# Power.net
KiCad netlist of a schematic drawn in Altium Designer
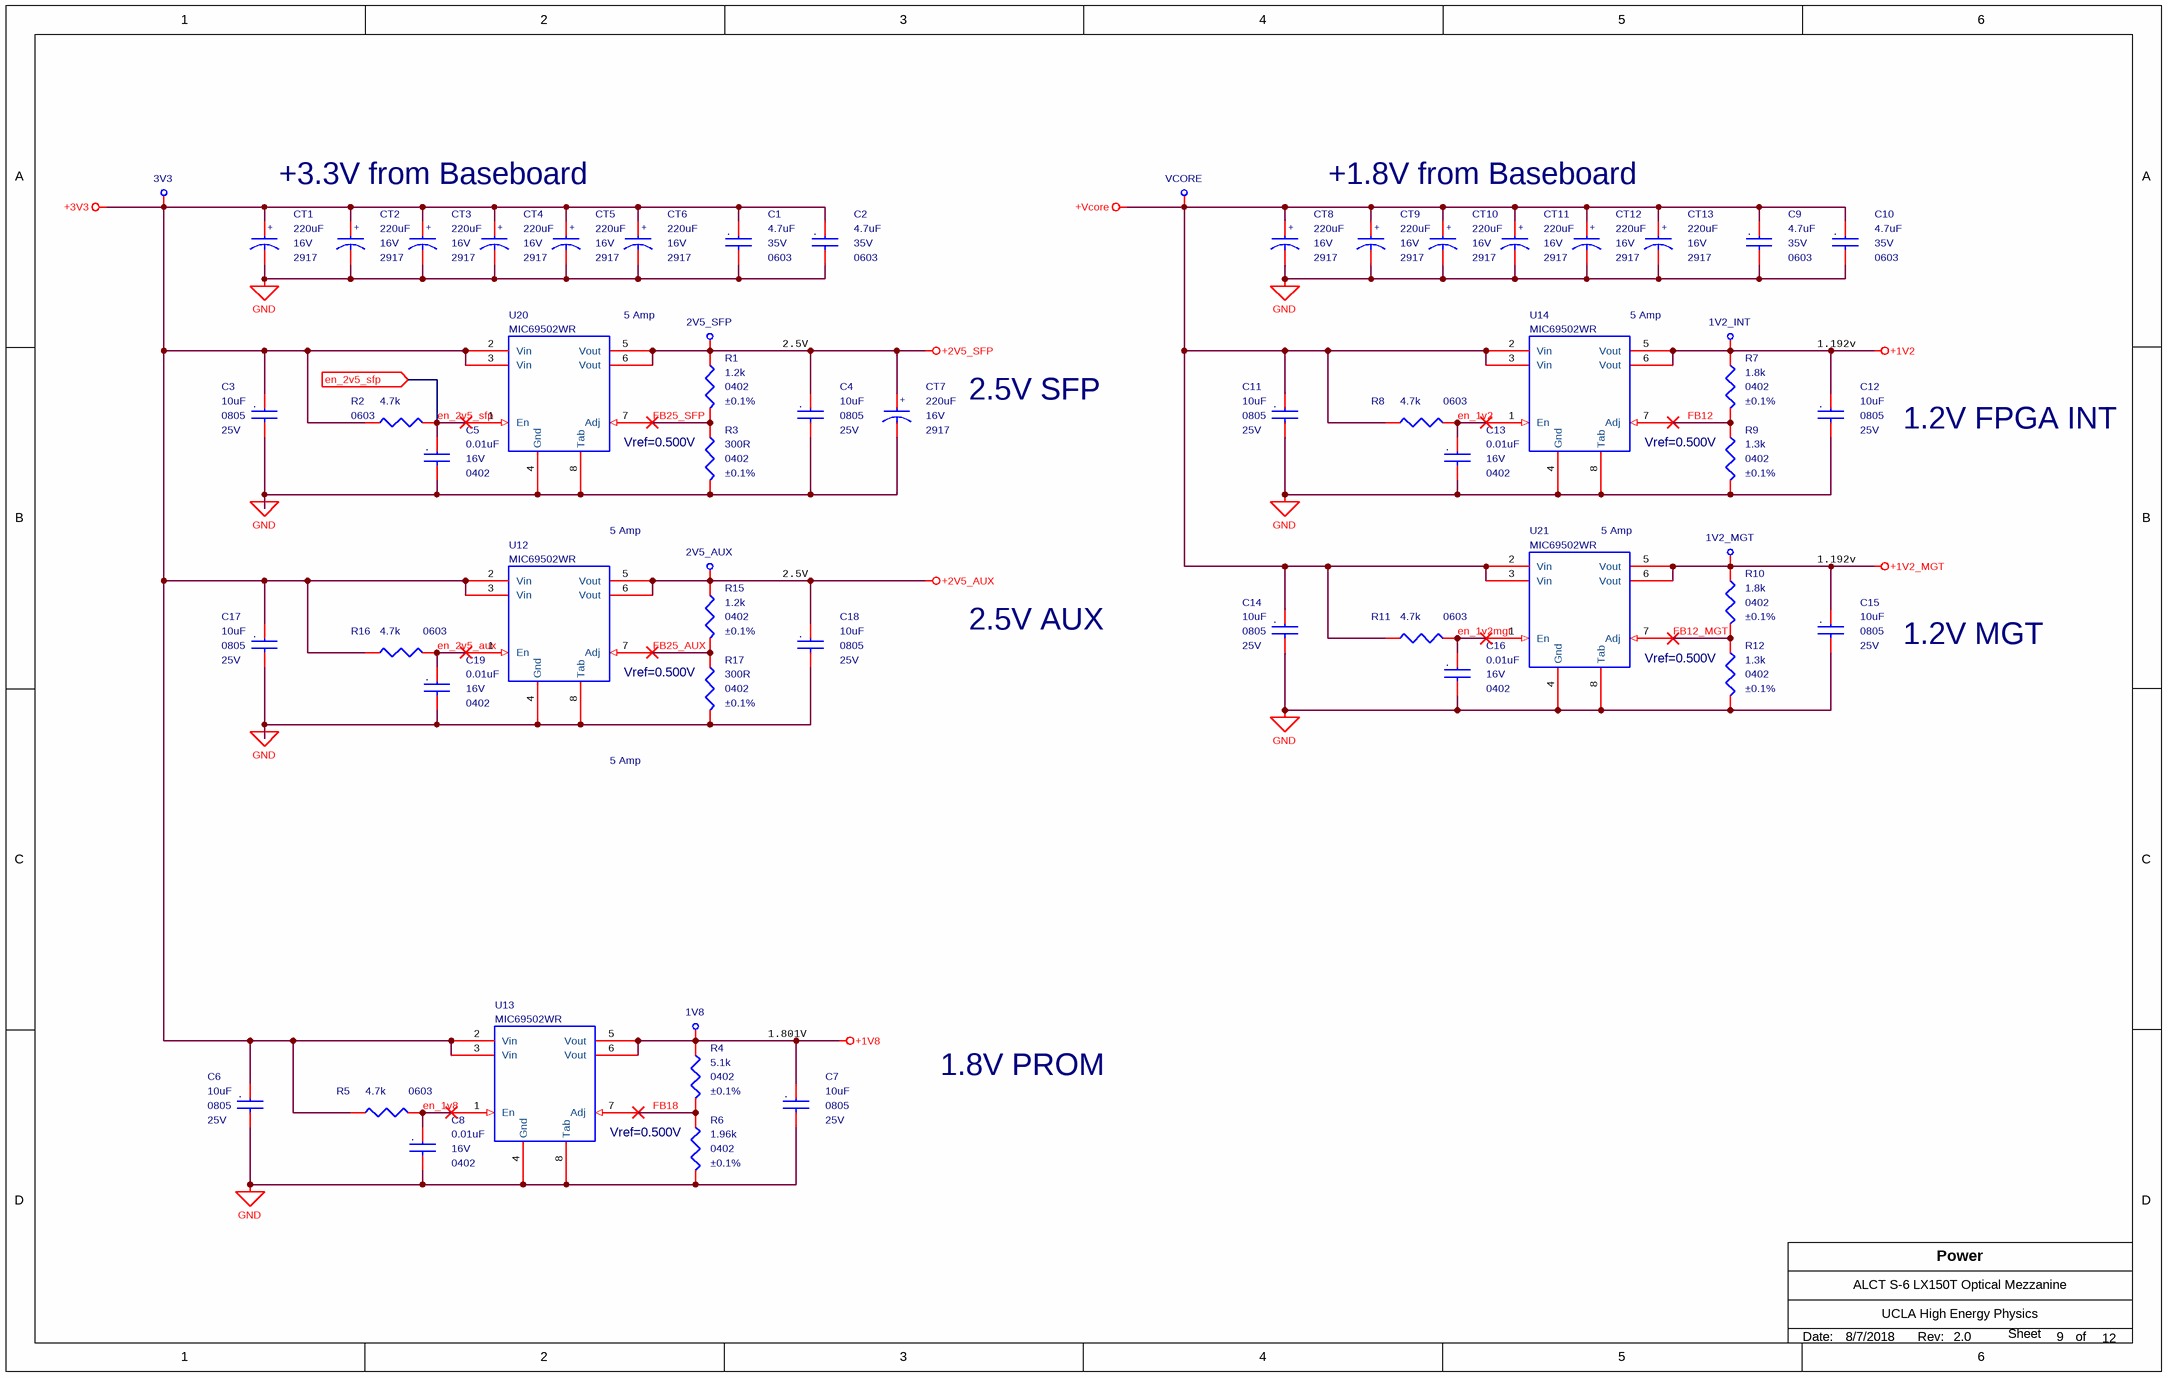
[diagram p0: Power.SchDoc]

(export (version "E")
  (design (tool "Eeschema 10.0.6"))
  (components
    (comp (ref "1V2_INT")
      (value "Test Point Via")
      (footprint "MC_S6/TH/TPVIA")
      (libsource (lib "ALCT_MEZ_SPARTAN6_Library") (part "TPVIA"))
    )
    (comp (ref "1V2_MGT")
      (value "Test Point Via")
      (footprint "MC_S6/TH/TPVIA")
      (libsource (lib "ALCT_MEZ_SPARTAN6_Library") (part "TPVIA"))
    )
    (comp (ref "1V8")
      (value "Test Point Via")
      (footprint "MC_S6/TH/TPVIA")
      (libsource (lib "ALCT_MEZ_SPARTAN6_Library") (part "TPVIA"))
    )
    (comp (ref "2V5_AUX")
      (value "Test Point Via")
      (footprint "MC_S6/TH/TPVIA")
      (libsource (lib "ALCT_MEZ_SPARTAN6_Library") (part "TPVIA"))
    )
    (comp (ref "2V5_SFP")
      (value "Test Point Via")
      (footprint "MC_S6/TH/TPVIA")
      (libsource (lib "ALCT_MEZ_SPARTAN6_Library") (part "TPVIA"))
    )
    (comp (ref "3V3")
      (value "Test Point Via")
      (footprint "MC_S6/TH/TPVIA")
      (libsource (lib "ALCT_MEZ_SPARTAN6_Library") (part "TPVIA"))
    )
    (comp (ref "C1")
      (value "4.7uF")
      (footprint "MC_S6/SM/C_0603_IPC")
      (description "CAP CER 4.7UF 35V X5R 0603")
      (fields
        (field (name "MANUFACTURER") "Murata")
        (field (name "MANUFACTURER PART NUMBER") "GRM188R6YA475KE15D")
        (field (name "VOLTAGE - RATED") "35V")
        (field (name "PACKAGE") "0603")
      )
      (libsource (lib "ALCT_MEZ_SPARTAN6_Library") (part "GRM188R6YA475KE15D"))
    )
    (comp (ref "C2")
      (value "4.7uF")
      (footprint "MC_S6/SM/C_0603_IPC")
      (description "CAP CER 4.7UF 35V X5R 0603")
      (fields
        (field (name "MANUFACTURER") "Murata")
        (field (name "MANUFACTURER PART NUMBER") "GRM188R6YA475KE15D")
        (field (name "VOLTAGE - RATED") "35V")
        (field (name "PACKAGE") "0603")
      )
      (libsource (lib "ALCT_MEZ_SPARTAN6_Library") (part "GRM188R6YA475KE15D"))
    )
    (comp (ref "C3")
      (value "10uF")
      (footprint "MC_S6/SM/C_0805_IPC")
      (description "CAP CER 10UF 25V X5R 0805")
      (fields
        (field (name "MANUFACTURER") "Murata Electronics North America")
        (field (name "MANUFACTURER PART NUMBER") "GRM21BR61E106KA73L")
        (field (name "VOLTAGE - RATED") "25V")
        (field (name "PACKAGE") "0805")
      )
      (libsource (lib "ALCT_MEZ_SPARTAN6_Library") (part "GRM21BR61E106KA73L"))
    )
    (comp (ref "C4")
      (value "10uF")
      (footprint "MC_S6/SM/C_0805_IPC")
      (description "CAP CER 10UF 25V X5R 0805")
      (fields
        (field (name "MANUFACTURER") "Murata Electronics North America")
        (field (name "MANUFACTURER PART NUMBER") "GRM21BR61E106KA73L")
        (field (name "VOLTAGE - RATED") "25V")
        (field (name "PACKAGE") "0805")
      )
      (libsource (lib "ALCT_MEZ_SPARTAN6_Library") (part "GRM21BR61E106KA73L"))
    )
    (comp (ref "C5")
      (value "0.01uF")
      (footprint "MC_S6/SM/C_0402_IPC")
      (description "CAP CER 10nF 16V X7R 0402")
      (fields
        (field (name "MANUFACTURER") "KEMET")
        (field (name "MANUFACTURER PART NUMBER") "C0402C103K4RACTU")
        (field (name "VOLTAGE - RATED") "16V")
        (field (name "PACKAGE") "0402")
      )
      (libsource (lib "ALCT_MEZ_SPARTAN6_Library") (part "C0402C103K4RACTU"))
    )
    (comp (ref "C6")
      (value "10uF")
      (footprint "MC_S6/SM/C_0805_IPC")
      (description "CAP CER 10UF 25V X5R 0805")
      (fields
        (field (name "MANUFACTURER") "Murata Electronics North America")
        (field (name "MANUFACTURER PART NUMBER") "GRM21BR61E106KA73L")
        (field (name "VOLTAGE - RATED") "25V")
        (field (name "PACKAGE") "0805")
      )
      (libsource (lib "ALCT_MEZ_SPARTAN6_Library") (part "GRM21BR61E106KA73L"))
    )
    (comp (ref "C7")
      (value "10uF")
      (footprint "MC_S6/SM/C_0805_IPC")
      (description "CAP CER 10UF 25V X5R 0805")
      (fields
        (field (name "MANUFACTURER") "Murata Electronics North America")
        (field (name "MANUFACTURER PART NUMBER") "GRM21BR61E106KA73L")
        (field (name "VOLTAGE - RATED") "25V")
        (field (name "PACKAGE") "0805")
      )
      (libsource (lib "ALCT_MEZ_SPARTAN6_Library") (part "GRM21BR61E106KA73L"))
    )
    (comp (ref "C8")
      (value "0.01uF")
      (footprint "MC_S6/SM/C_0402_IPC")
      (description "CAP CER 10nF 16V X7R 0402")
      (fields
        (field (name "MANUFACTURER") "KEMET")
        (field (name "MANUFACTURER PART NUMBER") "C0402C103K4RACTU")
        (field (name "VOLTAGE - RATED") "16V")
        (field (name "PACKAGE") "0402")
      )
      (libsource (lib "ALCT_MEZ_SPARTAN6_Library") (part "C0402C103K4RACTU"))
    )
    (comp (ref "C9")
      (value "4.7uF")
      (footprint "MC_S6/SM/C_0603_IPC")
      (description "CAP CER 4.7UF 35V X5R 0603")
      (fields
        (field (name "MANUFACTURER") "Murata")
        (field (name "MANUFACTURER PART NUMBER") "GRM188R6YA475KE15D")
        (field (name "VOLTAGE - RATED") "35V")
        (field (name "PACKAGE") "0603")
      )
      (libsource (lib "ALCT_MEZ_SPARTAN6_Library") (part "GRM188R6YA475KE15D"))
    )
    (comp (ref "C10")
      (value "4.7uF")
      (footprint "MC_S6/SM/C_0603_IPC")
      (description "CAP CER 4.7UF 35V X5R 0603")
      (fields
        (field (name "MANUFACTURER") "Murata")
        (field (name "MANUFACTURER PART NUMBER") "GRM188R6YA475KE15D")
        (field (name "VOLTAGE - RATED") "35V")
        (field (name "PACKAGE") "0603")
      )
      (libsource (lib "ALCT_MEZ_SPARTAN6_Library") (part "GRM188R6YA475KE15D"))
    )
    (comp (ref "C11")
      (value "10uF")
      (footprint "MC_S6/SM/C_0805_IPC")
      (description "CAP CER 10UF 25V X5R 0805")
      (fields
        (field (name "MANUFACTURER") "Murata Electronics North America")
        (field (name "MANUFACTURER PART NUMBER") "GRM21BR61E106KA73L")
        (field (name "VOLTAGE - RATED") "25V")
        (field (name "PACKAGE") "0805")
      )
      (libsource (lib "ALCT_MEZ_SPARTAN6_Library") (part "GRM21BR61E106KA73L"))
    )
    (comp (ref "C12")
      (value "10uF")
      (footprint "MC_S6/SM/C_0805_IPC")
      (description "CAP CER 10UF 25V X5R 0805")
      (fields
        (field (name "MANUFACTURER") "Murata Electronics North America")
        (field (name "MANUFACTURER PART NUMBER") "GRM21BR61E106KA73L")
        (field (name "VOLTAGE - RATED") "25V")
        (field (name "PACKAGE") "0805")
      )
      (libsource (lib "ALCT_MEZ_SPARTAN6_Library") (part "GRM21BR61E106KA73L"))
    )
    (comp (ref "C13")
      (value "0.01uF")
      (footprint "MC_S6/SM/C_0402_IPC")
      (description "CAP CER 10nF 16V X7R 0402")
      (fields
        (field (name "MANUFACTURER") "KEMET")
        (field (name "MANUFACTURER PART NUMBER") "C0402C103K4RACTU")
        (field (name "VOLTAGE - RATED") "16V")
        (field (name "PACKAGE") "0402")
      )
      (libsource (lib "ALCT_MEZ_SPARTAN6_Library") (part "C0402C103K4RACTU"))
    )
    (comp (ref "C14")
      (value "10uF")
      (footprint "MC_S6/SM/C_0805_IPC")
      (description "CAP CER 10UF 25V X5R 0805")
      (fields
        (field (name "MANUFACTURER") "Murata Electronics North America")
        (field (name "MANUFACTURER PART NUMBER") "GRM21BR61E106KA73L")
        (field (name "VOLTAGE - RATED") "25V")
        (field (name "PACKAGE") "0805")
      )
      (libsource (lib "ALCT_MEZ_SPARTAN6_Library") (part "GRM21BR61E106KA73L"))
    )
    (comp (ref "C15")
      (value "10uF")
      (footprint "MC_S6/SM/C_0805_IPC")
      (description "CAP CER 10UF 25V X5R 0805")
      (fields
        (field (name "MANUFACTURER") "Murata Electronics North America")
        (field (name "MANUFACTURER PART NUMBER") "GRM21BR61E106KA73L")
        (field (name "VOLTAGE - RATED") "25V")
        (field (name "PACKAGE") "0805")
      )
      (libsource (lib "ALCT_MEZ_SPARTAN6_Library") (part "GRM21BR61E106KA73L"))
    )
    (comp (ref "C16")
      (value "0.01uF")
      (footprint "MC_S6/SM/C_0402_IPC")
      (description "CAP CER 10nF 16V X7R 0402")
      (fields
        (field (name "MANUFACTURER") "KEMET")
        (field (name "MANUFACTURER PART NUMBER") "C0402C103K4RACTU")
        (field (name "VOLTAGE - RATED") "16V")
        (field (name "PACKAGE") "0402")
      )
      (libsource (lib "ALCT_MEZ_SPARTAN6_Library") (part "C0402C103K4RACTU"))
    )
    (comp (ref "C17")
      (value "10uF")
      (footprint "MC_S6/SM/C_0805_IPC")
      (description "CAP CER 10UF 25V X5R 0805")
      (fields
        (field (name "MANUFACTURER") "Murata Electronics North America")
        (field (name "MANUFACTURER PART NUMBER") "GRM21BR61E106KA73L")
        (field (name "VOLTAGE - RATED") "25V")
        (field (name "PACKAGE") "0805")
      )
      (libsource (lib "ALCT_MEZ_SPARTAN6_Library") (part "GRM21BR61E106KA73L"))
    )
    (comp (ref "C18")
      (value "10uF")
      (footprint "MC_S6/SM/C_0805_IPC")
      (description "CAP CER 10UF 25V X5R 0805")
      (fields
        (field (name "MANUFACTURER") "Murata Electronics North America")
        (field (name "MANUFACTURER PART NUMBER") "GRM21BR61E106KA73L")
        (field (name "VOLTAGE - RATED") "25V")
        (field (name "PACKAGE") "0805")
      )
      (libsource (lib "ALCT_MEZ_SPARTAN6_Library") (part "GRM21BR61E106KA73L"))
    )
    (comp (ref "C19")
      (value "0.01uF")
      (footprint "MC_S6/SM/C_0402_IPC")
      (description "CAP CER 10nF 16V X7R 0402")
      (fields
        (field (name "MANUFACTURER") "KEMET")
        (field (name "MANUFACTURER PART NUMBER") "C0402C103K4RACTU")
        (field (name "VOLTAGE - RATED") "16V")
        (field (name "PACKAGE") "0402")
      )
      (libsource (lib "ALCT_MEZ_SPARTAN6_Library") (part "C0402C103K4RACTU"))
    )
    (comp (ref "CT1")
      (value "220uF")
      (footprint "MC_S6/SM/CT_2917_D")
      (description "CAP TANT 220UF 16V 10% 2917")
      (fields
        (field (name "MANUFACTURER") "KEMET")
        (field (name "MANUFACTURER PART NUMBER") "T491D227K016AT")
        (field (name "VOLTAGE - RATED") "16V")
        (field (name "PACKAGE") "2917")
      )
      (libsource (lib "ALCT_MEZ_SPARTAN6_Library") (part "T491D227K016AT"))
    )
    (comp (ref "CT2")
      (value "220uF")
      (footprint "MC_S6/SM/CT_2917_D")
      (description "CAP TANT 220UF 16V 10% 2917")
      (fields
        (field (name "MANUFACTURER") "KEMET")
        (field (name "MANUFACTURER PART NUMBER") "T491D227K016AT")
        (field (name "VOLTAGE - RATED") "16V")
        (field (name "PACKAGE") "2917")
      )
      (libsource (lib "ALCT_MEZ_SPARTAN6_Library") (part "T491D227K016AT"))
    )
    (comp (ref "CT3")
      (value "220uF")
      (footprint "MC_S6/SM/CT_2917_D")
      (description "CAP TANT 220UF 16V 10% 2917")
      (fields
        (field (name "MANUFACTURER") "KEMET")
        (field (name "MANUFACTURER PART NUMBER") "T491D227K016AT")
        (field (name "VOLTAGE - RATED") "16V")
        (field (name "PACKAGE") "2917")
      )
      (libsource (lib "ALCT_MEZ_SPARTAN6_Library") (part "T491D227K016AT"))
    )
    (comp (ref "CT4")
      (value "220uF")
      (footprint "MC_S6/SM/CT_2917_D")
      (description "CAP TANT 220UF 16V 10% 2917")
      (fields
        (field (name "MANUFACTURER") "KEMET")
        (field (name "MANUFACTURER PART NUMBER") "T491D227K016AT")
        (field (name "VOLTAGE - RATED") "16V")
        (field (name "PACKAGE") "2917")
      )
      (libsource (lib "ALCT_MEZ_SPARTAN6_Library") (part "T491D227K016AT"))
    )
    (comp (ref "CT5")
      (value "220uF")
      (footprint "MC_S6/SM/CT_2917_D")
      (description "CAP TANT 220UF 16V 10% 2917")
      (fields
        (field (name "MANUFACTURER") "KEMET")
        (field (name "MANUFACTURER PART NUMBER") "T491D227K016AT")
        (field (name "VOLTAGE - RATED") "16V")
        (field (name "PACKAGE") "2917")
      )
      (libsource (lib "ALCT_MEZ_SPARTAN6_Library") (part "T491D227K016AT"))
    )
    (comp (ref "CT6")
      (value "220uF")
      (footprint "MC_S6/SM/CT_2917_D")
      (description "CAP TANT 220UF 16V 10% 2917")
      (fields
        (field (name "MANUFACTURER") "KEMET")
        (field (name "MANUFACTURER PART NUMBER") "T491D227K016AT")
        (field (name "VOLTAGE - RATED") "16V")
        (field (name "PACKAGE") "2917")
      )
      (libsource (lib "ALCT_MEZ_SPARTAN6_Library") (part "T491D227K016AT"))
    )
    (comp (ref "CT7")
      (value "220uF")
      (footprint "MC_S6/SM/CT_2917_D")
      (description "CAP TANT 220UF 16V 10% 2917")
      (fields
        (field (name "MANUFACTURER") "KEMET")
        (field (name "MANUFACTURER PART NUMBER") "T491D227K016AT")
        (field (name "VOLTAGE - RATED") "16V")
        (field (name "PACKAGE") "2917")
      )
      (libsource (lib "ALCT_MEZ_SPARTAN6_Library") (part "T491D227K016AT"))
    )
    (comp (ref "CT8")
      (value "220uF")
      (footprint "MC_S6/SM/CT_2917_D")
      (description "CAP TANT 220UF 16V 10% 2917")
      (fields
        (field (name "MANUFACTURER") "KEMET")
        (field (name "MANUFACTURER PART NUMBER") "T491D227K016AT")
        (field (name "VOLTAGE - RATED") "16V")
        (field (name "PACKAGE") "2917")
      )
      (libsource (lib "ALCT_MEZ_SPARTAN6_Library") (part "T491D227K016AT"))
    )
    (comp (ref "CT9")
      (value "220uF")
      (footprint "MC_S6/SM/CT_2917_D")
      (description "CAP TANT 220UF 16V 10% 2917")
      (fields
        (field (name "MANUFACTURER") "KEMET")
        (field (name "MANUFACTURER PART NUMBER") "T491D227K016AT")
        (field (name "VOLTAGE - RATED") "16V")
        (field (name "PACKAGE") "2917")
      )
      (libsource (lib "ALCT_MEZ_SPARTAN6_Library") (part "T491D227K016AT"))
    )
    (comp (ref "CT10")
      (value "220uF")
      (footprint "MC_S6/SM/CT_2917_D")
      (description "CAP TANT 220UF 16V 10% 2917")
      (fields
        (field (name "MANUFACTURER") "KEMET")
        (field (name "MANUFACTURER PART NUMBER") "T491D227K016AT")
        (field (name "VOLTAGE - RATED") "16V")
        (field (name "PACKAGE") "2917")
      )
      (libsource (lib "ALCT_MEZ_SPARTAN6_Library") (part "T491D227K016AT"))
    )
    (comp (ref "CT11")
      (value "220uF")
      (footprint "MC_S6/SM/CT_2917_D")
      (description "CAP TANT 220UF 16V 10% 2917")
      (fields
        (field (name "MANUFACTURER") "KEMET")
        (field (name "MANUFACTURER PART NUMBER") "T491D227K016AT")
        (field (name "VOLTAGE - RATED") "16V")
        (field (name "PACKAGE") "2917")
      )
      (libsource (lib "ALCT_MEZ_SPARTAN6_Library") (part "T491D227K016AT"))
    )
    (comp (ref "CT12")
      (value "220uF")
      (footprint "MC_S6/SM/CT_2917_D")
      (description "CAP TANT 220UF 16V 10% 2917")
      (fields
        (field (name "MANUFACTURER") "KEMET")
        (field (name "MANUFACTURER PART NUMBER") "T491D227K016AT")
        (field (name "VOLTAGE - RATED") "16V")
        (field (name "PACKAGE") "2917")
      )
      (libsource (lib "ALCT_MEZ_SPARTAN6_Library") (part "T491D227K016AT"))
    )
    (comp (ref "CT13")
      (value "220uF")
      (footprint "MC_S6/SM/CT_2917_D")
      (description "CAP TANT 220UF 16V 10% 2917")
      (fields
        (field (name "MANUFACTURER") "KEMET")
        (field (name "MANUFACTURER PART NUMBER") "T491D227K016AT")
        (field (name "VOLTAGE - RATED") "16V")
        (field (name "PACKAGE") "2917")
      )
      (libsource (lib "ALCT_MEZ_SPARTAN6_Library") (part "T491D227K016AT"))
    )
    (comp (ref "R1")
      (value "1.2k")
      (footprint "MC_S6/SM/R_0402_IPC")
      (description "RES SMD 1.2K OHM 0.1% 1/16W 0402")
      (fields
        (field (name "TOLERANCE") "±0.1%")
        (field (name "MANUFACTURER") "Panasonic Electronic Components")
        (field (name "MANUFACTURER PART NUMBER") "ERA-2AEB122X")
        (field (name "PACKAGE") "0402")
      )
      (libsource (lib "ALCT_MEZ_SPARTAN6_Library") (part "ERA-2AEB122X"))
    )
    (comp (ref "R2")
      (value "4.7k")
      (footprint "MC_S6/SM/R_0603_IPC")
      (description "RES SMD 4.7K OHM 1% 1/10W 0603")
      (fields
        (field (name "TOLERANCE") "±1%")
        (field (name "MANUFACTURER") "Bourns Inc.")
        (field (name "SUPPLIER DEVICE PACKAGE") "0603")
      )
      (libsource (lib "ALCT_MEZ_SPARTAN6_Library") (part "CR0603-FX-4701ELF"))
    )
    (comp (ref "R3")
      (value "300R")
      (footprint "MC_S6/SM/R_0402_IPC")
      (description "RES SMD 300 OHM 0.1% 1/16W 0402")
      (fields
        (field (name "TOLERANCE") "±0.1%")
        (field (name "MANUFACTURER") "Panasonic Electronic Components")
        (field (name "MANUFACTURER PART NUMBER") "ERA-2AEB301X")
        (field (name "PACKAGE") "0402")
      )
      (libsource (lib "ALCT_MEZ_SPARTAN6_Library") (part "ERA-2AEB301X"))
    )
    (comp (ref "R4")
      (value "5.1k")
      (footprint "MC_S6/SM/R_0402_IPC")
      (description "RES SMD 5.1K OHM 0.1% 1/16W 0402")
      (fields
        (field (name "TOLERANCE") "±0.1%")
        (field (name "MANUFACTURER") "Panasonic Electronic Components")
        (field (name "MANUFACTURER PART NUMBER") "ERA-2AEB512X")
        (field (name "SUPPLIER DEVICE PACKAGE") "0402")
      )
      (libsource (lib "ALCT_MEZ_SPARTAN6_Library") (part "ERA-2AEB512X"))
    )
    (comp (ref "R5")
      (value "4.7k")
      (footprint "MC_S6/SM/R_0603_IPC")
      (description "RES SMD 4.7K OHM 1% 1/10W 0603")
      (fields
        (field (name "TOLERANCE") "±1%")
        (field (name "MANUFACTURER") "Bourns Inc.")
        (field (name "SUPPLIER DEVICE PACKAGE") "0603")
      )
      (libsource (lib "ALCT_MEZ_SPARTAN6_Library") (part "CR0603-FX-4701ELF"))
    )
    (comp (ref "R6")
      (value "1.96k")
      (footprint "MC_S6/SM/R_0402_IPC")
      (description "RES SMD 1.96K OHM 0.1% 1/16W 0402")
      (fields
        (field (name "TOLERANCE") "±0.1%")
        (field (name "MANUFACTURER") "Panasonic Electronic Components")
        (field (name "MANUFACTURER PART NUMBER") "ERA-2AEB1961X")
        (field (name "PACKAGE") "0402")
      )
      (libsource (lib "ALCT_MEZ_SPARTAN6_Library") (part "ERA-2AEB1961X"))
    )
    (comp (ref "R7")
      (value "1.8k")
      (footprint "MC_S6/SM/R_0402_IPC")
      (description "RES SMD 1.8k OHM 0.1% 1/16W 0402")
      (fields
        (field (name "TOLERANCE") "±0.1%")
        (field (name "MANUFACTURER") "Panasonic Electronic Components")
        (field (name "MANUFACTURER PART NUMBER") "ERA-2AEB182X")
        (field (name "PACKAGE") "0402")
      )
      (libsource (lib "ALCT_MEZ_SPARTAN6_Library") (part "ERA-2AEB182X"))
    )
    (comp (ref "R8")
      (value "4.7k")
      (footprint "MC_S6/SM/R_0603_IPC")
      (description "RES SMD 4.7K OHM 1% 1/10W 0603")
      (fields
        (field (name "TOLERANCE") "±1%")
        (field (name "MANUFACTURER") "Bourns Inc.")
        (field (name "SUPPLIER DEVICE PACKAGE") "0603")
      )
      (libsource (lib "ALCT_MEZ_SPARTAN6_Library") (part "CR0603-FX-4701ELF"))
    )
    (comp (ref "R9")
      (value "1.3k")
      (footprint "MC_S6/SM/R_0402_IPC")
      (description "RES SMD 1.3k OHM 0.1% 1/16W 0402")
      (fields
        (field (name "TOLERANCE") "±0.1%")
        (field (name "MANUFACTURER") "Panasonic Electronic Components")
        (field (name "MANUFACTURER PART NUMBER") "ERA-2AEB132X")
        (field (name "SUPPLIER DEVICE PACKAGE") "0402")
      )
      (libsource (lib "ALCT_MEZ_SPARTAN6_Library") (part "ERA-2AEB132X"))
    )
    (comp (ref "R10")
      (value "1.8k")
      (footprint "MC_S6/SM/R_0402_IPC")
      (description "RES SMD 1.8k OHM 0.1% 1/16W 0402")
      (fields
        (field (name "TOLERANCE") "±0.1%")
        (field (name "MANUFACTURER") "Panasonic Electronic Components")
        (field (name "MANUFACTURER PART NUMBER") "ERA-2AEB182X")
        (field (name "SUPPLIER DEVICE PACKAGE") "0402")
      )
      (libsource (lib "ALCT_MEZ_SPARTAN6_Library") (part "ERA-2AEB182X"))
    )
    (comp (ref "R11")
      (value "4.7k")
      (footprint "MC_S6/SM/R_0603_IPC")
      (description "RES SMD 4.7K OHM 1% 1/10W 0603")
      (fields
        (field (name "TOLERANCE") "±1%")
        (field (name "MANUFACTURER") "Bourns Inc.")
        (field (name "SUPPLIER DEVICE PACKAGE") "0603")
      )
      (libsource (lib "ALCT_MEZ_SPARTAN6_Library") (part "CR0603-FX-4701ELF"))
    )
    (comp (ref "R12")
      (value "1.3k")
      (footprint "MC_S6/SM/R_0402_IPC")
      (description "RES SMD 1.3k OHM 0.1% 1/16W 0402")
      (fields
        (field (name "TOLERANCE") "±0.1%")
        (field (name "MANUFACTURER") "Panasonic Electronic Components")
        (field (name "MANUFACTURER PART NUMBER") "ERA-2AEB132X")
        (field (name "SUPPLIER DEVICE PACKAGE") "0402")
      )
      (libsource (lib "ALCT_MEZ_SPARTAN6_Library") (part "ERA-2AEB132X"))
    )
    (comp (ref "R15")
      (value "1.2k")
      (footprint "MC_S6/SM/R_0402_IPC")
      (description "RES SMD 1.2K OHM 0.1% 1/16W 0402")
      (fields
        (field (name "TOLERANCE") "±0.1%")
        (field (name "MANUFACTURER") "Panasonic Electronic Components")
        (field (name "MANUFACTURER PART NUMBER") "ERA-2AEB122X")
        (field (name "PACKAGE") "0402")
      )
      (libsource (lib "ALCT_MEZ_SPARTAN6_Library") (part "ERA-2AEB122X"))
    )
    (comp (ref "R16")
      (value "4.7k")
      (footprint "MC_S6/SM/R_0603_IPC")
      (description "RES SMD 4.7K OHM 1% 1/10W 0603")
      (fields
        (field (name "TOLERANCE") "±1%")
        (field (name "MANUFACTURER") "Bourns Inc.")
        (field (name "SUPPLIER DEVICE PACKAGE") "0603")
      )
      (libsource (lib "ALCT_MEZ_SPARTAN6_Library") (part "CR0603-FX-4701ELF"))
    )
    (comp (ref "R17")
      (value "300R")
      (footprint "MC_S6/SM/R_0402_IPC")
      (description "RES SMD 300 OHM 0.1% 1/16W 0402")
      (fields
        (field (name "TOLERANCE") "±0.1%")
        (field (name "MANUFACTURER") "Panasonic Electronic Components")
        (field (name "MANUFACTURER PART NUMBER") "ERA-2AEB301X")
        (field (name "PACKAGE") "0402")
      )
      (libsource (lib "ALCT_MEZ_SPARTAN6_Library") (part "ERA-2AEB301X"))
    )
    (comp (ref "U12")
      (value "MIC69502WR")
      (footprint "MC_S6/SM/SPAK7")
      (description "IC REG LDO ADJ 5A SPAK-7")
      (fields (field (name "MANUFACTURER") "Microchip Technology"))
      (libsource (lib "ALCT_MEZ_SPARTAN6_Library") (part "MIC69502WR"))
    )
    (comp (ref "U13")
      (value "MIC69502WR")
      (footprint "MC_S6/SM/SPAK7")
      (description "IC REG LDO ADJ 5A SPAK-7")
      (fields (field (name "MANUFACTURER") "Microchip Technology"))
      (libsource (lib "ALCT_MEZ_SPARTAN6_Library") (part "MIC69502WR"))
    )
    (comp (ref "U14")
      (value "MIC69502WR")
      (footprint "MC_S6/SM/SPAK7")
      (description "IC REG LDO ADJ 5A SPAK-7")
      (fields (field (name "MANUFACTURER") "Microchip Technology"))
      (libsource (lib "ALCT_MEZ_SPARTAN6_Library") (part "MIC69502WR"))
    )
    (comp (ref "U20")
      (value "MIC69502WR")
      (footprint "MC_S6/SM/SPAK7")
      (description "IC REG LDO ADJ 5A SPAK-7")
      (fields (field (name "MANUFACTURER") "Microchip Technology"))
      (libsource (lib "ALCT_MEZ_SPARTAN6_Library") (part "MIC69502WR"))
    )
    (comp (ref "U21")
      (value "MIC69502WR")
      (footprint "MC_S6/SM/SPAK7")
      (description "IC REG LDO ADJ 5A SPAK-7")
      (fields (field (name "MANUFACTURER") "Microchip Technology"))
      (libsource (lib "ALCT_MEZ_SPARTAN6_Library") (part "MIC69502WR"))
    )
    (comp (ref "VCORE")
      (value "Test Point Via")
      (footprint "MC_S6/TH/TPVIA")
      (libsource (lib "ALCT_MEZ_SPARTAN6_Library") (part "TPVIA"))
    )
  )
  (nets
    (net (code "1") (name "+1V2") (class "Default")
      (node (ref "1V2_INT") (pin "1") (pinfunction "In_1") (pintype "passive"))
      (node (ref "C12") (pin "1") (pinfunction "1_1") (pintype "passive"))
      (node (ref "R7") (pin "1") (pinfunction "1_1") (pintype "passive"))
      (node (ref "U14") (pin "5") (pinfunction "Vout_5") (pintype "power_in"))
      (node (ref "U14") (pin "6") (pinfunction "Vout_6") (pintype "power_in"))
    )
    (net (code "2") (name "+1V2_MGT") (class "Default")
      (node (ref "1V2_MGT") (pin "1") (pinfunction "In_1") (pintype "passive"))
      (node (ref "C15") (pin "1") (pinfunction "1_1") (pintype "passive"))
      (node (ref "R10") (pin "1") (pinfunction "1_1") (pintype "passive"))
      (node (ref "U21") (pin "5") (pinfunction "Vout_5") (pintype "power_in"))
      (node (ref "U21") (pin "6") (pinfunction "Vout_6") (pintype "power_in"))
    )
    (net (code "3") (name "+1V8") (class "Default")
      (node (ref "1V8") (pin "1") (pinfunction "In_1") (pintype "passive"))
      (node (ref "C7") (pin "1") (pinfunction "1_1") (pintype "passive"))
      (node (ref "R4") (pin "1") (pinfunction "1_1") (pintype "passive"))
      (node (ref "U13") (pin "5") (pinfunction "Vout_5") (pintype "power_in"))
      (node (ref "U13") (pin "6") (pinfunction "Vout_6") (pintype "power_in"))
    )
    (net (code "4") (name "+2V5_AUX") (class "Default")
      (node (ref "2V5_AUX") (pin "1") (pinfunction "In_1") (pintype "passive"))
      (node (ref "C18") (pin "1") (pinfunction "1_1") (pintype "passive"))
      (node (ref "R15") (pin "1") (pinfunction "1_1") (pintype "passive"))
      (node (ref "U12") (pin "5") (pinfunction "Vout_5") (pintype "power_in"))
      (node (ref "U12") (pin "6") (pinfunction "Vout_6") (pintype "power_in"))
    )
    (net (code "5") (name "+2V5_SFP") (class "Default")
      (node (ref "2V5_SFP") (pin "1") (pinfunction "In_1") (pintype "passive"))
      (node (ref "C4") (pin "1") (pinfunction "1_1") (pintype "passive"))
      (node (ref "CT7") (pin "1") (pinfunction "1_1") (pintype "passive"))
      (node (ref "R1") (pin "1") (pinfunction "1_1") (pintype "passive"))
      (node (ref "U20") (pin "5") (pinfunction "Vout_5") (pintype "power_in"))
      (node (ref "U20") (pin "6") (pinfunction "Vout_6") (pintype "power_in"))
    )
    (net (code "6") (name "+3V3") (class "Default")
      (node (ref "3V3") (pin "1") (pinfunction "In_1") (pintype "passive"))
      (node (ref "C1") (pin "1") (pinfunction "1_1") (pintype "passive"))
      (node (ref "C17") (pin "1") (pinfunction "1_1") (pintype "passive"))
      (node (ref "C2") (pin "1") (pinfunction "1_1") (pintype "passive"))
      (node (ref "C3") (pin "1") (pinfunction "1_1") (pintype "passive"))
      (node (ref "C6") (pin "1") (pinfunction "1_1") (pintype "passive"))
      (node (ref "CT1") (pin "1") (pinfunction "1_1") (pintype "passive"))
      (node (ref "CT2") (pin "1") (pinfunction "1_1") (pintype "passive"))
      (node (ref "CT3") (pin "1") (pinfunction "1_1") (pintype "passive"))
      (node (ref "CT4") (pin "1") (pinfunction "1_1") (pintype "passive"))
      (node (ref "CT5") (pin "1") (pinfunction "1_1") (pintype "passive"))
      (node (ref "CT6") (pin "1") (pinfunction "1_1") (pintype "passive"))
      (node (ref "R16") (pin "1") (pinfunction "1_1") (pintype "passive"))
      (node (ref "R2") (pin "1") (pinfunction "1_1") (pintype "passive"))
      (node (ref "R5") (pin "1") (pinfunction "1_1") (pintype "passive"))
      (node (ref "U12") (pin "2") (pinfunction "Vin_2") (pintype "power_in"))
      (node (ref "U12") (pin "3") (pinfunction "Vin_3") (pintype "power_in"))
      (node (ref "U13") (pin "2") (pinfunction "Vin_2") (pintype "power_in"))
      (node (ref "U13") (pin "3") (pinfunction "Vin_3") (pintype "power_in"))
      (node (ref "U20") (pin "2") (pinfunction "Vin_2") (pintype "power_in"))
      (node (ref "U20") (pin "3") (pinfunction "Vin_3") (pintype "power_in"))
    )
    (net (code "7") (name "+Vcore") (class "Default")
      (node (ref "C10") (pin "1") (pinfunction "1_1") (pintype "passive"))
      (node (ref "C11") (pin "1") (pinfunction "1_1") (pintype "passive"))
      (node (ref "C14") (pin "1") (pinfunction "1_1") (pintype "passive"))
      (node (ref "C9") (pin "1") (pinfunction "1_1") (pintype "passive"))
      (node (ref "CT10") (pin "1") (pinfunction "1_1") (pintype "passive"))
      (node (ref "CT11") (pin "1") (pinfunction "1_1") (pintype "passive"))
      (node (ref "CT12") (pin "1") (pinfunction "1_1") (pintype "passive"))
      (node (ref "CT13") (pin "1") (pinfunction "1_1") (pintype "passive"))
      (node (ref "CT8") (pin "1") (pinfunction "1_1") (pintype "passive"))
      (node (ref "CT9") (pin "1") (pinfunction "1_1") (pintype "passive"))
      (node (ref "R11") (pin "1") (pinfunction "1_1") (pintype "passive"))
      (node (ref "R8") (pin "1") (pinfunction "1_1") (pintype "passive"))
      (node (ref "U14") (pin "2") (pinfunction "Vin_2") (pintype "power_in"))
      (node (ref "U14") (pin "3") (pinfunction "Vin_3") (pintype "power_in"))
      (node (ref "U21") (pin "2") (pinfunction "Vin_2") (pintype "power_in"))
      (node (ref "U21") (pin "3") (pinfunction "Vin_3") (pintype "power_in"))
      (node (ref "VCORE") (pin "1") (pinfunction "In_1") (pintype "passive"))
    )
    (net (code "8") (name "/FB12") (class "Default")
      (node (ref "R7") (pin "2") (pinfunction "2_2") (pintype "passive"))
      (node (ref "R9") (pin "1") (pinfunction "1_1") (pintype "passive"))
      (node (ref "U14") (pin "7") (pinfunction "Adj_7") (pintype "input"))
    )
    (net (code "9") (name "/FB12_MGT") (class "Default")
      (node (ref "R10") (pin "2") (pinfunction "2_2") (pintype "passive"))
      (node (ref "R12") (pin "1") (pinfunction "1_1") (pintype "passive"))
      (node (ref "U21") (pin "7") (pinfunction "Adj_7") (pintype "input"))
    )
    (net (code "10") (name "/FB18") (class "Default")
      (node (ref "R4") (pin "2") (pinfunction "2_2") (pintype "passive"))
      (node (ref "R6") (pin "1") (pinfunction "1_1") (pintype "passive"))
      (node (ref "U13") (pin "7") (pinfunction "Adj_7") (pintype "input"))
    )
    (net (code "11") (name "/FB25_AUX") (class "Default")
      (node (ref "R15") (pin "2") (pinfunction "2_2") (pintype "passive"))
      (node (ref "R17") (pin "1") (pinfunction "1_1") (pintype "passive"))
      (node (ref "U12") (pin "7") (pinfunction "Adj_7") (pintype "input"))
    )
    (net (code "12") (name "/FB25_SFP") (class "Default")
      (node (ref "R1") (pin "2") (pinfunction "2_2") (pintype "passive"))
      (node (ref "R3") (pin "1") (pinfunction "1_1") (pintype "passive"))
      (node (ref "U20") (pin "7") (pinfunction "Adj_7") (pintype "input"))
    )
    (net (code "13") (name "/en_1v2") (class "Default")
      (node (ref "C13") (pin "1") (pinfunction "1_1") (pintype "passive"))
      (node (ref "R8") (pin "2") (pinfunction "2_2") (pintype "passive"))
      (node (ref "U14") (pin "1") (pinfunction "En_1") (pintype "input"))
    )
    (net (code "14") (name "/en_1v2mgt") (class "Default")
      (node (ref "C16") (pin "1") (pinfunction "1_1") (pintype "passive"))
      (node (ref "R11") (pin "2") (pinfunction "2_2") (pintype "passive"))
      (node (ref "U21") (pin "1") (pinfunction "En_1") (pintype "input"))
    )
    (net (code "15") (name "/en_1v8") (class "Default")
      (node (ref "C8") (pin "1") (pinfunction "1_1") (pintype "passive"))
      (node (ref "R5") (pin "2") (pinfunction "2_2") (pintype "passive"))
      (node (ref "U13") (pin "1") (pinfunction "En_1") (pintype "input"))
    )
    (net (code "16") (name "/en_2v5_aux") (class "Default")
      (node (ref "C19") (pin "1") (pinfunction "1_1") (pintype "passive"))
      (node (ref "R16") (pin "2") (pinfunction "2_2") (pintype "passive"))
      (node (ref "U12") (pin "1") (pinfunction "En_1") (pintype "input"))
    )
    (net (code "17") (name "/en_2v5_sfp") (class "Default")
      (node (ref "C5") (pin "1") (pinfunction "1_1") (pintype "passive"))
      (node (ref "R2") (pin "2") (pinfunction "2_2") (pintype "passive"))
      (node (ref "U20") (pin "1") (pinfunction "En_1") (pintype "input"))
    )
    (net (code "18") (name "GND") (class "Default")
      (node (ref "C1") (pin "2") (pinfunction "2_2") (pintype "passive"))
      (node (ref "C10") (pin "2") (pinfunction "2_2") (pintype "passive"))
      (node (ref "C11") (pin "2") (pinfunction "2_2") (pintype "passive"))
      (node (ref "C12") (pin "2") (pinfunction "2_2") (pintype "passive"))
      (node (ref "C13") (pin "2") (pinfunction "2_2") (pintype "passive"))
      (node (ref "C14") (pin "2") (pinfunction "2_2") (pintype "passive"))
      (node (ref "C15") (pin "2") (pinfunction "2_2") (pintype "passive"))
      (node (ref "C16") (pin "2") (pinfunction "2_2") (pintype "passive"))
      (node (ref "C17") (pin "2") (pinfunction "2_2") (pintype "passive"))
      (node (ref "C18") (pin "2") (pinfunction "2_2") (pintype "passive"))
      (node (ref "C19") (pin "2") (pinfunction "2_2") (pintype "passive"))
      (node (ref "C2") (pin "2") (pinfunction "2_2") (pintype "passive"))
      (node (ref "C3") (pin "2") (pinfunction "2_2") (pintype "passive"))
      (node (ref "C4") (pin "2") (pinfunction "2_2") (pintype "passive"))
      (node (ref "C5") (pin "2") (pinfunction "2_2") (pintype "passive"))
      (node (ref "C6") (pin "2") (pinfunction "2_2") (pintype "passive"))
      (node (ref "C7") (pin "2") (pinfunction "2_2") (pintype "passive"))
      (node (ref "C8") (pin "2") (pinfunction "2_2") (pintype "passive"))
      (node (ref "C9") (pin "2") (pinfunction "2_2") (pintype "passive"))
      (node (ref "CT1") (pin "2") (pinfunction "2_2") (pintype "passive"))
      (node (ref "CT10") (pin "2") (pinfunction "2_2") (pintype "passive"))
      (node (ref "CT11") (pin "2") (pinfunction "2_2") (pintype "passive"))
      (node (ref "CT12") (pin "2") (pinfunction "2_2") (pintype "passive"))
      (node (ref "CT13") (pin "2") (pinfunction "2_2") (pintype "passive"))
      (node (ref "CT2") (pin "2") (pinfunction "2_2") (pintype "passive"))
      (node (ref "CT3") (pin "2") (pinfunction "2_2") (pintype "passive"))
      (node (ref "CT4") (pin "2") (pinfunction "2_2") (pintype "passive"))
      (node (ref "CT5") (pin "2") (pinfunction "2_2") (pintype "passive"))
      (node (ref "CT6") (pin "2") (pinfunction "2_2") (pintype "passive"))
      (node (ref "CT7") (pin "2") (pinfunction "2_2") (pintype "passive"))
      (node (ref "CT8") (pin "2") (pinfunction "2_2") (pintype "passive"))
      (node (ref "CT9") (pin "2") (pinfunction "2_2") (pintype "passive"))
      (node (ref "R12") (pin "2") (pinfunction "2_2") (pintype "passive"))
      (node (ref "R17") (pin "2") (pinfunction "2_2") (pintype "passive"))
      (node (ref "R3") (pin "2") (pinfunction "2_2") (pintype "passive"))
      (node (ref "R6") (pin "2") (pinfunction "2_2") (pintype "passive"))
      (node (ref "R9") (pin "2") (pinfunction "2_2") (pintype "passive"))
      (node (ref "U12") (pin "4") (pinfunction "Gnd_4") (pintype "power_in"))
      (node (ref "U12") (pin "8") (pinfunction "Tab_8") (pintype "power_in"))
      (node (ref "U13") (pin "4") (pinfunction "Gnd_4") (pintype "power_in"))
      (node (ref "U13") (pin "8") (pinfunction "Tab_8") (pintype "power_in"))
      (node (ref "U14") (pin "4") (pinfunction "Gnd_4") (pintype "power_in"))
      (node (ref "U14") (pin "8") (pinfunction "Tab_8") (pintype "power_in"))
      (node (ref "U20") (pin "4") (pinfunction "Gnd_4") (pintype "power_in"))
      (node (ref "U20") (pin "8") (pinfunction "Tab_8") (pintype "power_in"))
      (node (ref "U21") (pin "4") (pinfunction "Gnd_4") (pintype "power_in"))
      (node (ref "U21") (pin "8") (pinfunction "Tab_8") (pintype "power_in"))
    )
  )
)
